# Sensor_Infra.net
KiCad netlist of a schematic drawn in Altium Designer
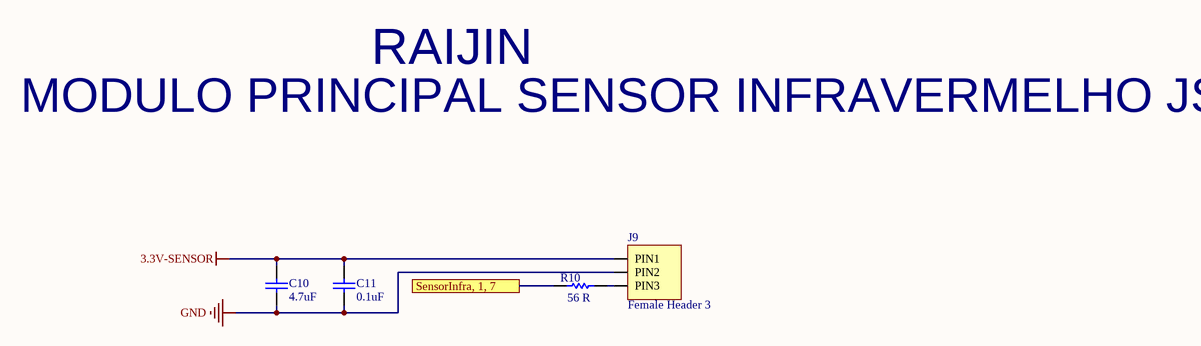
[diagram p0: Sensor Infra.SchDoc]

(export (version "E")
  (design (tool "Eeschema 10.0.6"))
  (components
    (comp (ref "C10")
      (value "4.7uF")
      (footprint "C0805")
      (description "CAP CER 4.7uF 25V 20% 0805")
      (fields
        (field (name "MANUFACTURER") "Walsin")
        (field (name "PART NUMBER") "0805X475M250CT")
        (field (name "LIBRARY CONTROL - PERSON THAT CHECKED SCHEMATIC") "Guilherme")
        (field (name "LIBRARY CONTROL - PERSON THAT DID THE LAST UPDATE SCHEMATIC") "Marcos")
      )
      (libsource (lib "Uai!Tecas") (part "0805X475M250CT"))
    )
    (comp (ref "C11")
      (value "0.1uF")
      (footprint "C0805")
      (description "CAP CER 0.1uF 25V X7R 0805")
      (fields
        (field (name "MANUFACTURER") "AVX")
        (field (name "PART NUMBER") "08053C104KAT2A")
        (field (name "LIBRARY CONTROL - PERSON THAT CHECKED FOOTPRINT") "Nikaum")
        (field (name "LIBRARY CONTROL - PERSON THAT CHECKED SCHEMATIC") "Nikaum")
        (field (name "LIBRARY CONTROL - PERSON THAT DID THE LAST UPDATE FOOTPRINT") "Nikaum")
        (field (name "LIBRARY CONTROL - PERSON THAT DID THE LAST UPDATE SCHEMATIC") "Nikaum")
      )
      (libsource (lib "Uai!Tecas") (part "08053C104KAT2A"))
    )
    (comp (ref "J9")
      (value "Female Header 3")
      (footprint "FEMALE HEADER 3")
      (libsource (lib "Uai!Tecas") (part "Female Header 3"))
    )
    (comp (ref "R10")
      (value "56 R")
      (footprint "RESISTOR_0603")
      (description "RES SMD 56 OHMS 1% 1/10W 0603")
      (fields
        (field (name "MANUFACTURER") "Bourns")
        (field (name "PART NUMBER") "CR0603-FX-56R0ELF")
        (field (name "LIBRARY CONTROL - PERSON THAT CHECKED FOOTPRINT") "Nikaum")
        (field (name "LIBRARY CONTROL - PERSON THAT CHECKED SCHEMATIC") "Nikaum")
        (field (name "LIBRARY CONTROL - PERSON THAT DID THE LAST UPDATE FOOTPRINT") "Nicolas")
        (field (name "LIBRARY CONTROL - PERSON THAT DID THE LAST UPDATE SCHEMATIC") "Nikaum")
      )
      (libsource (lib "Uai!Tecas") (part "CR0603-FX-56R0ELF"))
    )
  )
  (nets
    (net (code "1") (name "/SensorInfra, 1, 7") (class "Default")
      (node (ref "R10") (pin "1") (pinfunction "1_1") (pintype "passive"))
    )
    (net (code "2") (name "3.3V-SENSOR") (class "Default")
      (node (ref "C10") (pin "2") (pinfunction "2_2") (pintype "passive"))
      (node (ref "C11") (pin "2") (pinfunction "2_2") (pintype "passive"))
      (node (ref "J9") (pin "PIN1") (pinfunction "PIN1_PIN1") (pintype "passive"))
    )
    (net (code "3") (name "GND") (class "Default")
      (node (ref "C10") (pin "1") (pinfunction "1_1") (pintype "passive"))
      (node (ref "C11") (pin "1") (pinfunction "1_1") (pintype "passive"))
      (node (ref "J9") (pin "PIN2") (pinfunction "PIN2_PIN2") (pintype "passive"))
    )
    (net (code "4") (name "Net-(J9-PadPIN3)") (class "Default")
      (node (ref "J9") (pin "PIN3") (pinfunction "PIN3_PIN3") (pintype "passive"))
      (node (ref "R10") (pin "2") (pinfunction "2_2") (pintype "passive"))
    )
  )
)
